# lcd-i2c.net
KiCad netlist of a schematic drawn in EAGLE
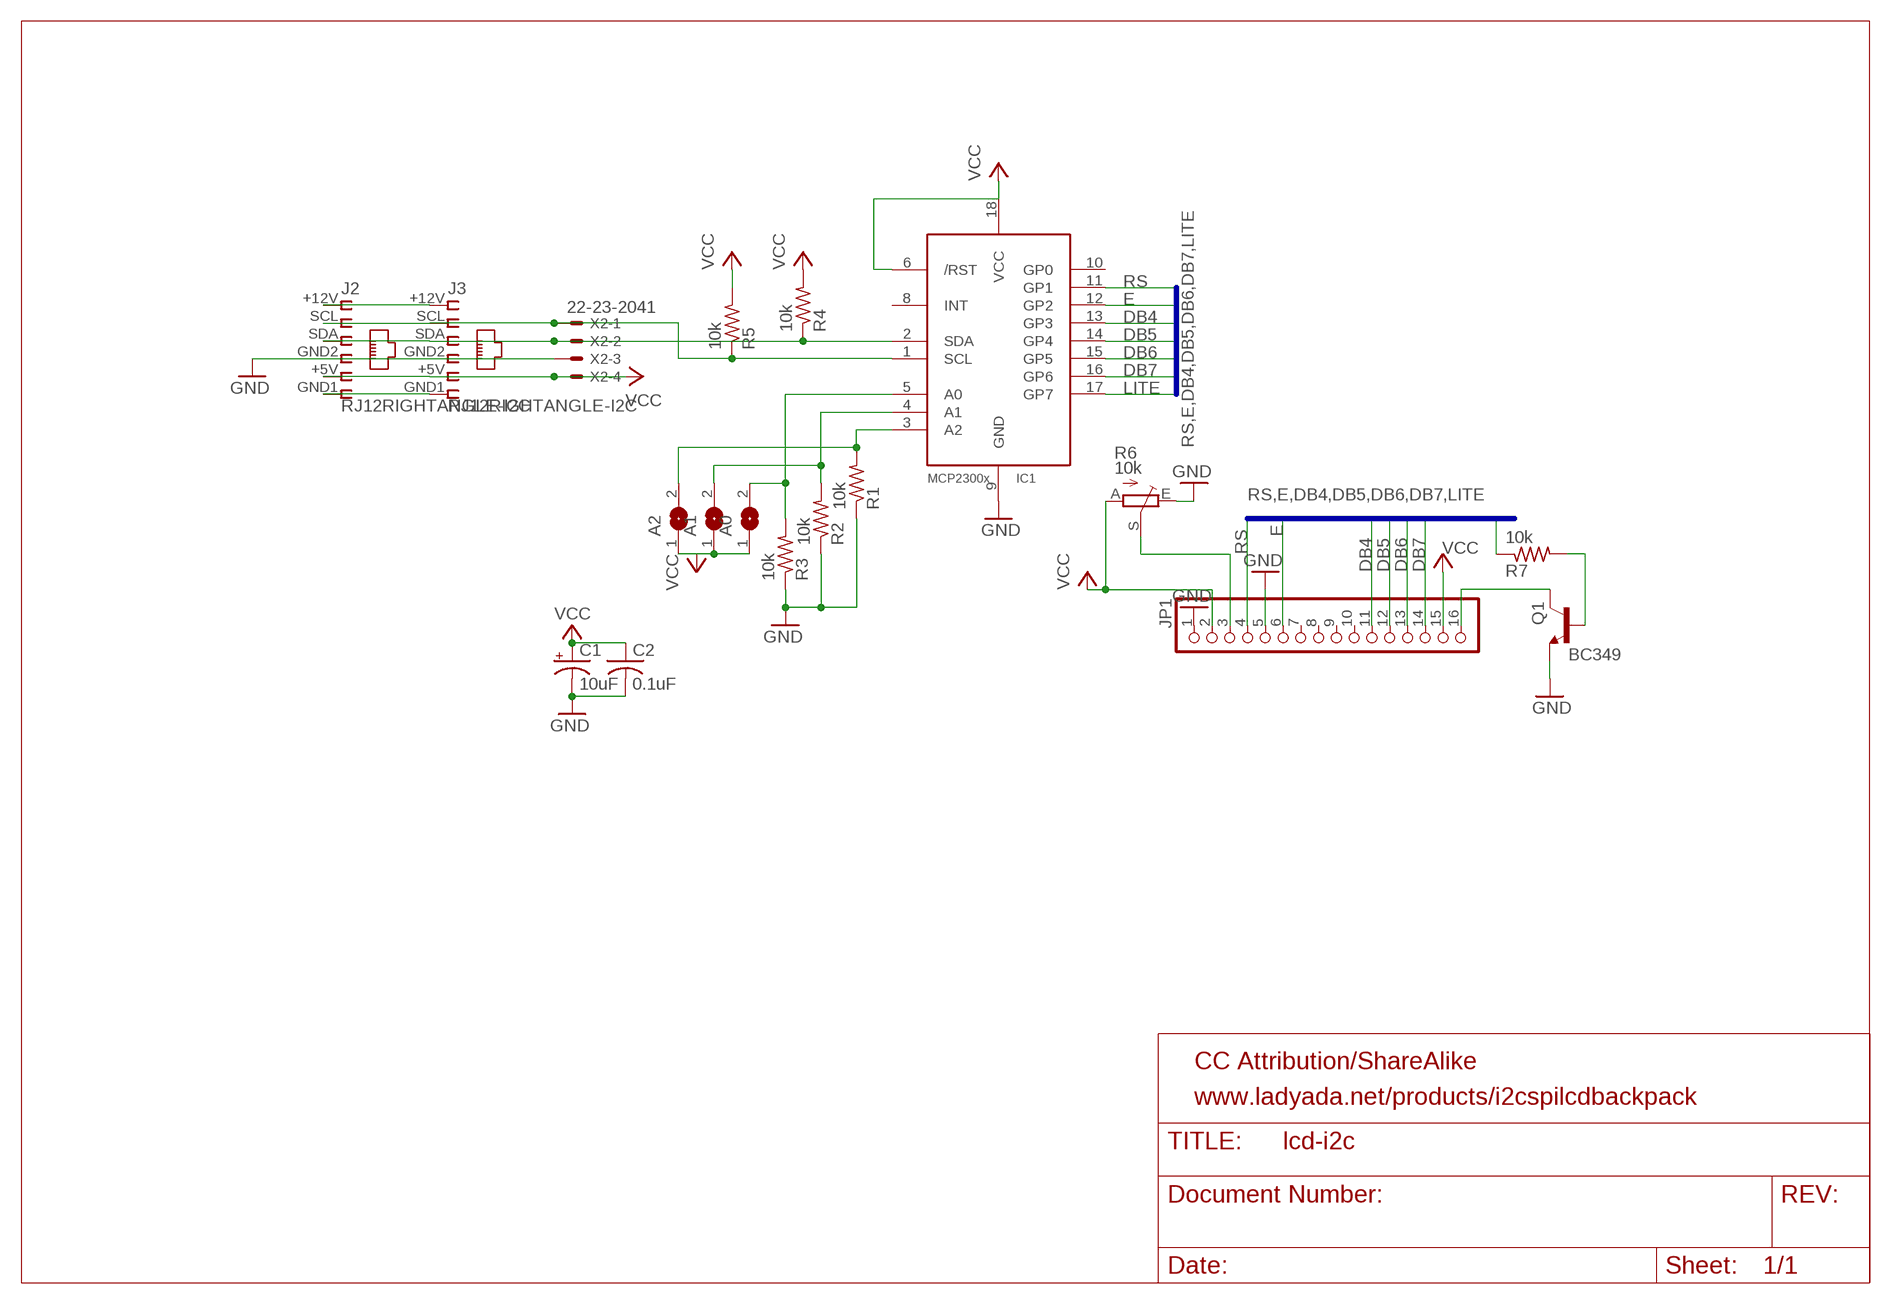
[diagram p0: schematic, sheet 1]

(export (version "E")
  (design (tool "Eeschema 10.0.6"))
  (components
    (comp (ref "A0") (value "SJ") (footprint "eagle-import:SJ") (libsource (lib "eagle-import") (part "SJ")))
    (comp (ref "A1") (value "SJ") (footprint "eagle-import:SJ") (libsource (lib "eagle-import") (part "SJ")))
    (comp (ref "A2") (value "SJ") (footprint "eagle-import:SJ") (libsource (lib "eagle-import") (part "SJ")))
    (comp (ref "C1")
      (value "10uF")
      (footprint "eagle-import:A_3216-18R")
      (libsource (lib "eagle-import") (part "CPOL-USA/3216-18R"))
    )
    (comp (ref "C2")
      (value "0.1uF")
      (footprint "eagle-import:C1206")
      (libsource (lib "eagle-import") (part "C-USC1206"))
    )
    (comp (ref "IC1")
      (value "MCP2300X/P")
      (footprint "eagle-import:DIL18")
      (libsource (lib "eagle-import") (part "MCP2300X/P"))
    )
    (comp (ref "J2")
      (value "RJ12RIGHTANGLE-I2C")
      (footprint "eagle-import:RJ12-RIGHTANGLE-I2C")
      (libsource (lib "eagle-import") (part "RJ12RIGHTANGLE-I2C"))
    )
    (comp (ref "J3")
      (value "RJ12RIGHTANGLE-I2C")
      (footprint "eagle-import:RJ12-RIGHTANGLE-I2C")
      (libsource (lib "eagle-import") (part "RJ12RIGHTANGLE-I2C"))
    )
    (comp (ref "JP1")
      (value "PINHD-1X16")
      (footprint "eagle-import:1X16")
      (libsource (lib "eagle-import") (part "PINHD-1X16"))
    )
    (comp (ref "Q1")
      (value "BC349")
      (footprint "eagle-import:TO92-EBC")
      (libsource (lib "eagle-import") (part "-NPN-TO92-EBCBC317"))
    )
    (comp (ref "R1")
      (value "10k")
      (footprint "eagle-import:M1206")
      (libsource (lib "eagle-import") (part "R-US_M1206"))
    )
    (comp (ref "R2")
      (value "10k")
      (footprint "eagle-import:M1206")
      (libsource (lib "eagle-import") (part "R-US_M1206"))
    )
    (comp (ref "R3")
      (value "10k")
      (footprint "eagle-import:M1206")
      (libsource (lib "eagle-import") (part "R-US_M1206"))
    )
    (comp (ref "R4")
      (value "10k")
      (footprint "eagle-import:M1206")
      (libsource (lib "eagle-import") (part "R-US_M1206"))
    )
    (comp (ref "R5")
      (value "10k")
      (footprint "eagle-import:M1206")
      (libsource (lib "eagle-import") (part "R-US_M1206"))
    )
    (comp (ref "R6")
      (value "10k")
      (footprint "eagle-import:CA6V")
      (libsource (lib "eagle-import") (part "TRIM_EU-CA6V"))
    )
    (comp (ref "R7")
      (value "10k")
      (footprint "eagle-import:M1206")
      (libsource (lib "eagle-import") (part "R-US_M1206"))
    )
    (comp (ref "X2")
      (value "22-23-2041")
      (footprint "eagle-import:22-23-2041")
      (fields (field (name "MF") "MOLEX"))
      (libsource (lib "eagle-import") (part "22-23-2041"))
    )
  )
  (nets
    (net (code "1") (name "/DB4") (class "Default")
      (node (ref "IC1") (pin "13") (pinfunction "GP3_13") (pintype "bidirectional"))
      (node (ref "JP1") (pin "11") (pinfunction "11_11") (pintype "passive"))
    )
    (net (code "2") (name "/DB5") (class "Default")
      (node (ref "IC1") (pin "14") (pinfunction "GP4_14") (pintype "bidirectional"))
      (node (ref "JP1") (pin "12") (pinfunction "12_12") (pintype "passive"))
    )
    (net (code "3") (name "/DB6") (class "Default")
      (node (ref "IC1") (pin "15") (pinfunction "GP5_15") (pintype "bidirectional"))
      (node (ref "JP1") (pin "13") (pinfunction "13_13") (pintype "passive"))
    )
    (net (code "4") (name "/DB7") (class "Default")
      (node (ref "IC1") (pin "16") (pinfunction "GP6_16") (pintype "bidirectional"))
      (node (ref "JP1") (pin "14") (pinfunction "14_14") (pintype "passive"))
    )
    (net (code "5") (name "/E") (class "Default")
      (node (ref "IC1") (pin "12") (pinfunction "GP2_12") (pintype "bidirectional"))
      (node (ref "JP1") (pin "6") (pinfunction "6_6") (pintype "passive"))
    )
    (net (code "6") (name "/LITE") (class "Default")
      (node (ref "IC1") (pin "17") (pinfunction "GP7_17") (pintype "bidirectional"))
      (node (ref "R7") (pin "1") (pinfunction "1_1") (pintype "passive"))
    )
    (net (code "7") (name "/RS") (class "Default")
      (node (ref "IC1") (pin "11") (pinfunction "GP1_11") (pintype "bidirectional"))
      (node (ref "JP1") (pin "4") (pinfunction "4_4") (pintype "passive"))
    )
    (net (code "9") (name "GND") (class "Default")
      (node (ref "C1") (pin "-") (pinfunction "-_-") (pintype "passive"))
      (node (ref "C2") (pin "2") (pinfunction "2_2") (pintype "passive"))
      (node (ref "IC1") (pin "9") (pinfunction "GND_9") (pintype "power_in"))
      (node (ref "J2") (pin "GND2") (pinfunction "4_GND2") (pintype "power_in"))
      (node (ref "J3") (pin "GND2") (pinfunction "4_GND2") (pintype "power_in"))
      (node (ref "JP1") (pin "1") (pinfunction "1_1") (pintype "passive"))
      (node (ref "JP1") (pin "5") (pinfunction "5_5") (pintype "passive"))
      (node (ref "Q1") (pin "E") (pinfunction "E_E") (pintype "passive"))
      (node (ref "R1") (pin "1") (pinfunction "1_1") (pintype "passive"))
      (node (ref "R2") (pin "1") (pinfunction "1_1") (pintype "passive"))
      (node (ref "R3") (pin "1") (pinfunction "1_1") (pintype "passive"))
      (node (ref "R6") (pin "E") (pinfunction "E_E") (pintype "passive"))
      (node (ref "X2") (pin "3") (pinfunction "S_3") (pintype "passive"))
    )
    (net (code "10") (name "Net-(IC1-A0)") (class "Default")
      (node (ref "A0") (pin "2") (pinfunction "2_2") (pintype "passive"))
      (node (ref "IC1") (pin "5") (pinfunction "A0_5") (pintype "input"))
      (node (ref "R3") (pin "2") (pinfunction "2_2") (pintype "passive"))
    )
    (net (code "11") (name "Net-(IC1-A1)") (class "Default")
      (node (ref "A1") (pin "2") (pinfunction "2_2") (pintype "passive"))
      (node (ref "IC1") (pin "4") (pinfunction "A1_4") (pintype "input"))
      (node (ref "R2") (pin "2") (pinfunction "2_2") (pintype "passive"))
    )
    (net (code "12") (name "Net-(IC1-A2)") (class "Default")
      (node (ref "A2") (pin "2") (pinfunction "2_2") (pintype "passive"))
      (node (ref "IC1") (pin "3") (pinfunction "A2_3") (pintype "input"))
      (node (ref "R1") (pin "2") (pinfunction "2_2") (pintype "passive"))
    )
    (net (code "13") (name "Net-(IC1-SCL)") (class "Default")
      (node (ref "IC1") (pin "1") (pinfunction "SCL_1") (pintype "bidirectional"))
      (node (ref "J2") (pin "SCL") (pinfunction "2_SCL") (pintype "bidirectional"))
      (node (ref "J3") (pin "SCL") (pinfunction "2_SCL") (pintype "bidirectional"))
      (node (ref "R5") (pin "1") (pinfunction "1_1") (pintype "passive"))
      (node (ref "X2") (pin "1") (pinfunction "S_1") (pintype "passive"))
    )
    (net (code "14") (name "Net-(IC1-SDA)") (class "Default")
      (node (ref "IC1") (pin "2") (pinfunction "SDA_2") (pintype "bidirectional"))
      (node (ref "J2") (pin "SDA") (pinfunction "3_SDA") (pintype "bidirectional"))
      (node (ref "J3") (pin "SDA") (pinfunction "3_SDA") (pintype "bidirectional"))
      (node (ref "R4") (pin "1") (pinfunction "1_1") (pintype "passive"))
      (node (ref "X2") (pin "2") (pinfunction "S_2") (pintype "passive"))
    )
    (net (code "15") (name "Net-(J2-1)") (class "Default")
      (node (ref "J2") (pin "+12V") (pinfunction "1_+12V") (pintype "power_in"))
      (node (ref "J3") (pin "+12V") (pinfunction "1_+12V") (pintype "power_in"))
    )
    (net (code "16") (name "Net-(J2-6)") (class "Default")
      (node (ref "J2") (pin "GND1") (pinfunction "6_GND1") (pintype "power_in"))
      (node (ref "J3") (pin "GND1") (pinfunction "6_GND1") (pintype "power_in"))
    )
    (net (code "17") (name "Net-(JP1-Pad3)") (class "Default")
      (node (ref "JP1") (pin "3") (pinfunction "3_3") (pintype "passive"))
      (node (ref "R6") (pin "S") (pinfunction "S_S") (pintype "passive"))
    )
    (net (code "18") (name "Net-(JP1-Pad16)") (class "Default")
      (node (ref "JP1") (pin "16") (pinfunction "16_16") (pintype "passive"))
      (node (ref "Q1") (pin "C") (pinfunction "C_C") (pintype "passive"))
    )
    (net (code "19") (name "Net-(Q1-PadB)") (class "Default")
      (node (ref "Q1") (pin "B") (pinfunction "B_B") (pintype "passive"))
      (node (ref "R7") (pin "2") (pinfunction "2_2") (pintype "passive"))
    )
    (net (code "20") (name "VCC") (class "Default")
      (node (ref "A0") (pin "1") (pinfunction "1_1") (pintype "passive"))
      (node (ref "A1") (pin "1") (pinfunction "1_1") (pintype "passive"))
      (node (ref "A2") (pin "1") (pinfunction "1_1") (pintype "passive"))
      (node (ref "C1") (pin "+") (pinfunction "+_+") (pintype "passive"))
      (node (ref "C2") (pin "1") (pinfunction "1_1") (pintype "passive"))
      (node (ref "IC1") (pin "18") (pinfunction "VCC_18") (pintype "power_in"))
      (node (ref "IC1") (pin "6") (pinfunction "/RST_6") (pintype "input"))
      (node (ref "J2") (pin "+5V") (pinfunction "5_+5V") (pintype "power_in"))
      (node (ref "J3") (pin "+5V") (pinfunction "5_+5V") (pintype "power_in"))
      (node (ref "JP1") (pin "15") (pinfunction "15_15") (pintype "passive"))
      (node (ref "JP1") (pin "2") (pinfunction "2_2") (pintype "passive"))
      (node (ref "R4") (pin "2") (pinfunction "2_2") (pintype "passive"))
      (node (ref "R5") (pin "2") (pinfunction "2_2") (pintype "passive"))
      (node (ref "R6") (pin "A") (pinfunction "A_A") (pintype "passive"))
      (node (ref "X2") (pin "4") (pinfunction "S_4") (pintype "passive"))
    )
    (net (code "21") (name "unconnected-(IC1-GP0-Pad10)") (class "Default")
      (node (ref "IC1") (pin "10") (pinfunction "GP0_10") (pintype "bidirectional"))
    )
    (net (code "22") (name "unconnected-(IC1-INT-Pad8)") (class "Default")
      (node (ref "IC1") (pin "8") (pinfunction "INT_8") (pintype "output"))
    )
    (net (code "23") (name "unconnected-(JP1-Pad7)") (class "Default")
      (node (ref "JP1") (pin "7") (pinfunction "7_7") (pintype "passive"))
    )
    (net (code "24") (name "unconnected-(JP1-Pad8)") (class "Default")
      (node (ref "JP1") (pin "8") (pinfunction "8_8") (pintype "passive"))
    )
    (net (code "25") (name "unconnected-(JP1-Pad9)") (class "Default")
      (node (ref "JP1") (pin "9") (pinfunction "9_9") (pintype "passive"))
    )
    (net (code "26") (name "unconnected-(JP1-Pad10)") (class "Default")
      (node (ref "JP1") (pin "10") (pinfunction "10_10") (pintype "passive"))
    )
  )
)
